# Connection.net
KiCad netlist of a schematic drawn in EAGLE
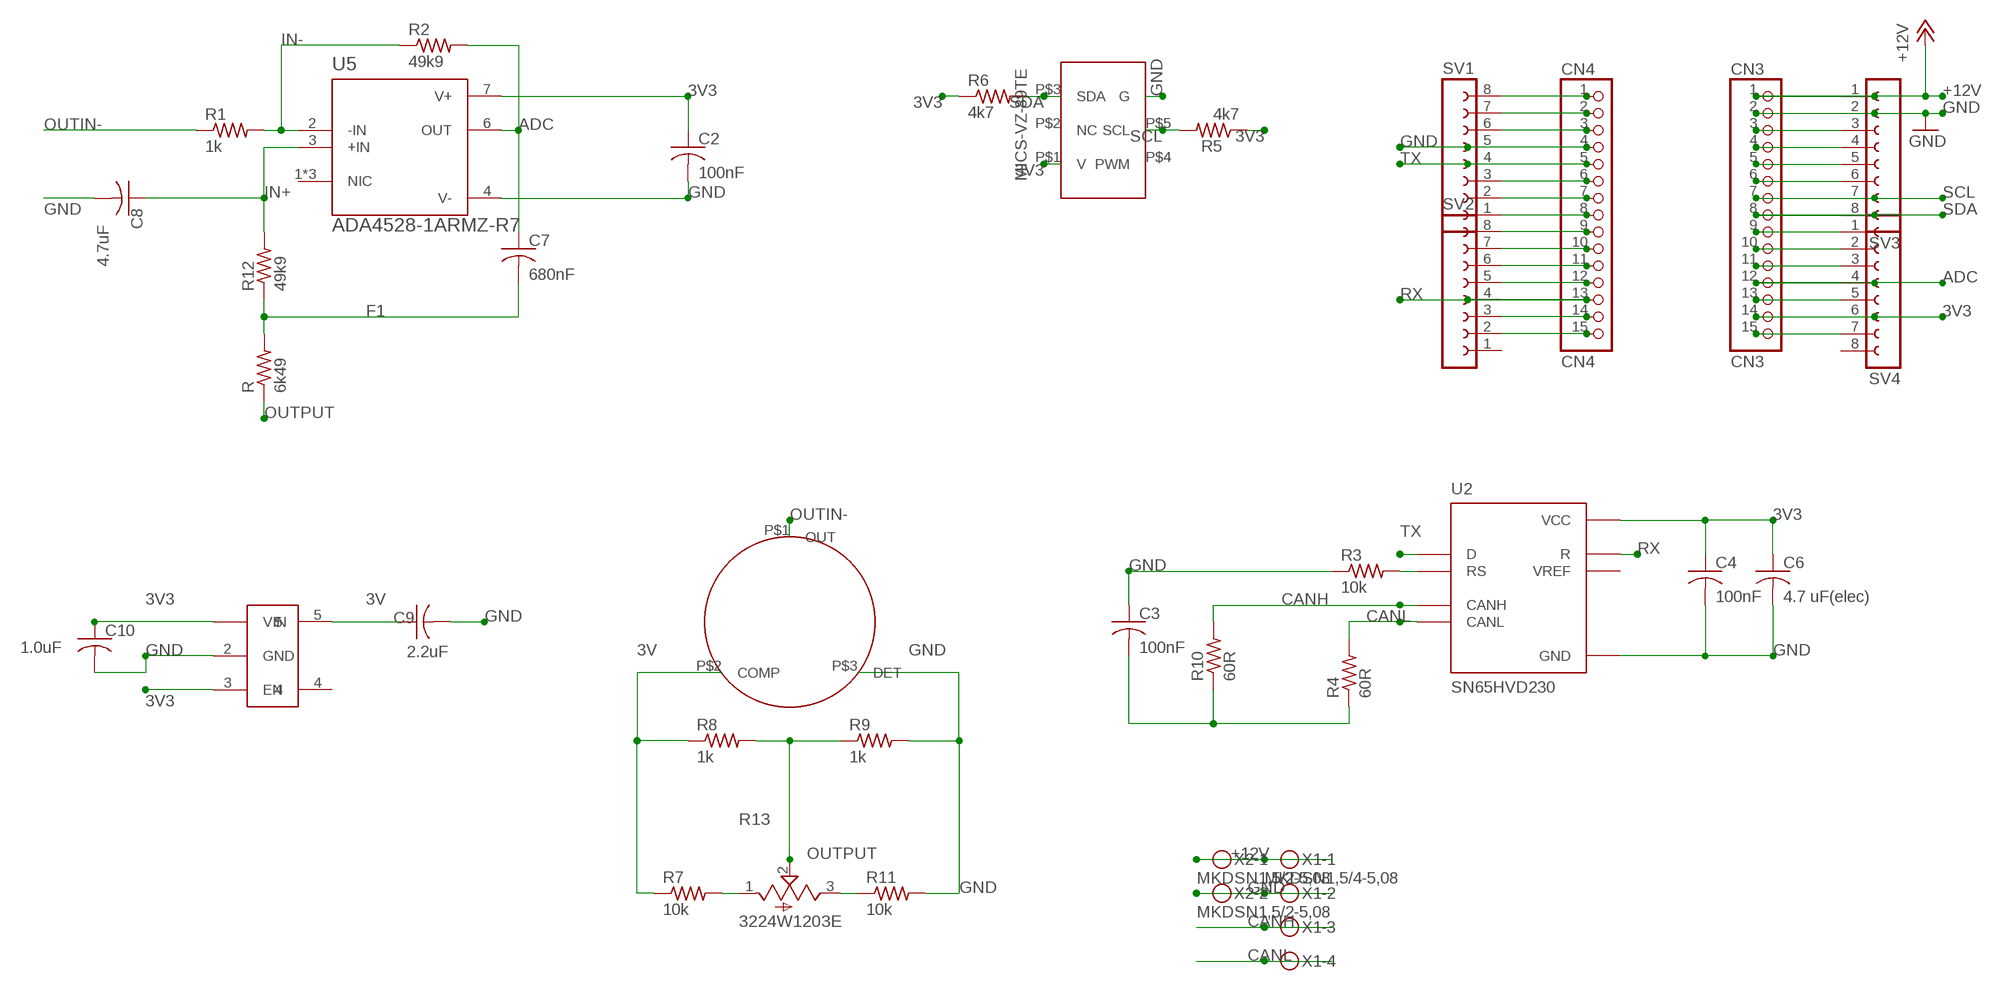
[diagram p0: schematic, sheet 1]

(export (version "E")
  (design (tool "Eeschema 10.0.6"))
  (components
    (comp (ref "C2")
      (value "100nF")
      (footprint "eagle-import:C0402")
      (libsource (lib "eagle-import") (part "C-USC0402"))
    )
    (comp (ref "C3")
      (value "100nF")
      (footprint "eagle-import:C0402")
      (libsource (lib "eagle-import") (part "C-USC0402"))
    )
    (comp (ref "C4")
      (value "100nF")
      (footprint "eagle-import:C0402")
      (libsource (lib "eagle-import") (part "C-USC0402"))
    )
    (comp (ref "C6")
      (value "4.7 uF(elec)")
      (footprint "eagle-import:C0603")
      (libsource (lib "eagle-import") (part "C-USC0603"))
    )
    (comp (ref "C7")
      (value "680nF")
      (footprint "eagle-import:C1206")
      (libsource (lib "eagle-import") (part "C-USC1206"))
    )
    (comp (ref "C8")
      (value "4.7uF")
      (footprint "eagle-import:C1206")
      (libsource (lib "eagle-import") (part "C-USC1206"))
    )
    (comp (ref "C9")
      (value "2.2uF")
      (footprint "eagle-import:C0603")
      (libsource (lib "eagle-import") (part "C-USC0603"))
    )
    (comp (ref "C10")
      (value "1.0uF")
      (footprint "eagle-import:C0805")
      (libsource (lib "eagle-import") (part "C-USC0805"))
    )
    (comp (ref "CN3")
      (value "CN3")
      (footprint "eagle-import:1X15")
      (libsource (lib "eagle-import") (part "PINHD-1X15"))
    )
    (comp (ref "CN4")
      (value "CN4")
      (footprint "eagle-import:1X15")
      (libsource (lib "eagle-import") (part "PINHD-1X15"))
    )
    (comp (ref "R")
      (value "6k49")
      (footprint "eagle-import:R0603")
      (libsource (lib "eagle-import") (part "R-US_R0603"))
    )
    (comp (ref "R1")
      (value "1k")
      (footprint "eagle-import:R0805")
      (libsource (lib "eagle-import") (part "R-US_R0805"))
    )
    (comp (ref "R2")
      (value "49k9")
      (footprint "eagle-import:R0603")
      (libsource (lib "eagle-import") (part "R-US_R0603"))
    )
    (comp (ref "R3")
      (value "10k")
      (footprint "eagle-import:M1206")
      (libsource (lib "eagle-import") (part "R-US_M1206"))
    )
    (comp (ref "R4")
      (value "60R")
      (footprint "eagle-import:R0603")
      (libsource (lib "eagle-import") (part "R-US_R0603"))
    )
    (comp (ref "R5")
      (value "4k7")
      (footprint "eagle-import:M1206")
      (libsource (lib "eagle-import") (part "R-US_M1206"))
    )
    (comp (ref "R6")
      (value "4k7")
      (footprint "eagle-import:M1206")
      (libsource (lib "eagle-import") (part "R-US_M1206"))
    )
    (comp (ref "R7")
      (value "10k")
      (footprint "eagle-import:M1206")
      (libsource (lib "eagle-import") (part "R-US_M1206"))
    )
    (comp (ref "R8")
      (value "1k")
      (footprint "eagle-import:R0805")
      (libsource (lib "eagle-import") (part "R-US_R0805"))
    )
    (comp (ref "R9")
      (value "1k")
      (footprint "eagle-import:R0805")
      (libsource (lib "eagle-import") (part "R-US_R0805"))
    )
    (comp (ref "R10")
      (value "60R")
      (footprint "eagle-import:R0603")
      (libsource (lib "eagle-import") (part "R-US_R0603"))
    )
    (comp (ref "R11")
      (value "10k")
      (footprint "eagle-import:M1206")
      (libsource (lib "eagle-import") (part "R-US_M1206"))
    )
    (comp (ref "R12")
      (value "49k9")
      (footprint "eagle-import:R0603")
      (libsource (lib "eagle-import") (part "R-US_R0603"))
    )
    (comp (ref "R13")
      (value "3224W1203E")
      (footprint "eagle-import:TRIM_3224W1203E")
      (fields (field (name "MF") "Bourns") (field (name "MP") "3224W-1-203E"))
      (libsource (lib "eagle-import") (part "3224W1203E"))
    )
    (comp (ref "SV1")
      (value "FE08-1")
      (footprint "eagle-import:FE08")
      (libsource (lib "eagle-import") (part "FE08-1"))
    )
    (comp (ref "SV2")
      (value "FE08-1")
      (footprint "eagle-import:FE08")
      (libsource (lib "eagle-import") (part "FE08-1"))
    )
    (comp (ref "SV3")
      (value "FE08-1")
      (footprint "eagle-import:FE08")
      (libsource (lib "eagle-import") (part "FE08-1"))
    )
    (comp (ref "SV4")
      (value "FE08-1")
      (footprint "eagle-import:FE08")
      (libsource (lib "eagle-import") (part "FE08-1"))
    )
    (comp (ref "U$1")
      (value "MP7227")
      (footprint "eagle-import:MP7227_FP")
      (libsource (lib "eagle-import") (part "MP7227"))
    )
    (comp (ref "U$3")
      (value "MIC5233")
      (footprint "eagle-import:MIC5233")
      (libsource (lib "eagle-import") (part "MIC5233"))
    )
    (comp (ref "U$4")
      (value "MICS-VZ-89TE")
      (footprint "eagle-import:MICS-VZ-89TE_FP")
      (libsource (lib "eagle-import") (part "MICS-VZ-89TE"))
    )
    (comp (ref "U2")
      (value "SN65HVD230")
      (footprint "eagle-import:SOIC127P599X175-8N")
      (fields (field (name "MF") "Texas Instruments"))
      (libsource (lib "eagle-import") (part "SN65HVD230"))
    )
    (comp (ref "U5")
      (value "ADA4528-1ARMZ-R7")
      (footprint "eagle-import:SOP65P490X110-8N")
      (fields (field (name "MF") "Analog Devices"))
      (libsource (lib "eagle-import") (part "ADA4528-1ARMZ-R7"))
    )
    (comp (ref "X1")
      (value "MKDSN1,5/4-5,08")
      (footprint "eagle-import:MKDSN1,5_4-5,08")
      (libsource (lib "eagle-import") (part "MKDSN1,5/4-5,08"))
    )
    (comp (ref "X2")
      (value "MKDSN1,5/2-5,08")
      (footprint "eagle-import:MKDSN1,5_2-5,08")
      (libsource (lib "eagle-import") (part "MKDSN1,5/2-5,08"))
    )
  )
  (nets
    (net (code "1") (name "+12V") (class "Default")
      (node (ref "CN3") (pin "1") (pinfunction "1_1") (pintype "passive"))
      (node (ref "SV3") (pin "1") (pinfunction "1_1") (pintype "passive"))
      (node (ref "X1") (pin "1") (pinfunction "KL_1") (pintype "passive"))
      (node (ref "X2") (pin "1") (pinfunction "KL_1") (pintype "passive"))
    )
    (net (code "2") (name "/3V") (class "Default")
      (node (ref "C9") (pin "1") (pinfunction "1_1") (pintype "passive"))
      (node (ref "R7") (pin "1") (pinfunction "1_1") (pintype "passive"))
      (node (ref "R8") (pin "1") (pinfunction "1_1") (pintype "passive"))
      (node (ref "U$1") (pin "P$2") (pinfunction "COMP_P$2") (pintype "bidirectional"))
      (node (ref "U$3") (pin "5") (pinfunction "5_5") (pintype "bidirectional"))
    )
    (net (code "3") (name "/3V3") (class "Default")
      (node (ref "C10") (pin "1") (pinfunction "1_1") (pintype "passive"))
      (node (ref "C2") (pin "1") (pinfunction "1_1") (pintype "passive"))
      (node (ref "C4") (pin "1") (pinfunction "1_1") (pintype "passive"))
      (node (ref "C6") (pin "1") (pinfunction "1_1") (pintype "passive"))
      (node (ref "CN3") (pin "14") (pinfunction "14_14") (pintype "passive"))
      (node (ref "R5") (pin "1") (pinfunction "1_1") (pintype "passive"))
      (node (ref "R6") (pin "1") (pinfunction "1_1") (pintype "passive"))
      (node (ref "SV4") (pin "6") (pinfunction "6_6") (pintype "passive"))
      (node (ref "U$3") (pin "1") (pinfunction "VIN_1") (pintype "bidirectional"))
      (node (ref "U$3") (pin "3") (pinfunction "EN_3") (pintype "bidirectional"))
      (node (ref "U$4") (pin "P$1") (pinfunction "V_P$1") (pintype "bidirectional"))
      (node (ref "U2") (pin "3") (pinfunction "VCC_3") (pintype "power_in"))
      (node (ref "U5") (pin "7") (pinfunction "V+_7") (pintype "power_in"))
    )
    (net (code "4") (name "/ADC") (class "Default")
      (node (ref "C7") (pin "1") (pinfunction "1_1") (pintype "passive"))
      (node (ref "CN3") (pin "12") (pinfunction "12_12") (pintype "passive"))
      (node (ref "R2") (pin "2") (pinfunction "2_2") (pintype "passive"))
      (node (ref "SV4") (pin "4") (pinfunction "4_4") (pintype "passive"))
      (node (ref "U5") (pin "6") (pinfunction "OUT_6") (pintype "output"))
    )
    (net (code "5") (name "/CANH") (class "Default")
      (node (ref "R10") (pin "2") (pinfunction "2_2") (pintype "passive"))
      (node (ref "U2") (pin "7") (pinfunction "CANH_7") (pintype "bidirectional"))
      (node (ref "X1") (pin "3") (pinfunction "KL_3") (pintype "passive"))
    )
    (net (code "6") (name "/CANL") (class "Default")
      (node (ref "R4") (pin "2") (pinfunction "2_2") (pintype "passive"))
      (node (ref "U2") (pin "6") (pinfunction "CANL_6") (pintype "bidirectional"))
      (node (ref "X1") (pin "4") (pinfunction "KL_4") (pintype "passive"))
    )
    (net (code "7") (name "/F1") (class "Default")
      (node (ref "C7") (pin "2") (pinfunction "2_2") (pintype "passive"))
      (node (ref "R") (pin "2") (pinfunction "2_2") (pintype "passive"))
      (node (ref "R12") (pin "1") (pinfunction "1_1") (pintype "passive"))
    )
    (net (code "8") (name "/IN+") (class "Default")
      (node (ref "C8") (pin "1") (pinfunction "1_1") (pintype "passive"))
      (node (ref "R12") (pin "2") (pinfunction "2_2") (pintype "passive"))
      (node (ref "U5") (pin "3") (pinfunction "+IN_3") (pintype "input"))
    )
    (net (code "9") (name "/IN-") (class "Default")
      (node (ref "R1") (pin "2") (pinfunction "2_2") (pintype "passive"))
      (node (ref "R2") (pin "1") (pinfunction "1_1") (pintype "passive"))
      (node (ref "U5") (pin "2") (pinfunction "-IN_2") (pintype "input"))
    )
    (net (code "10") (name "/OUTIN-") (class "Default")
      (node (ref "R1") (pin "1") (pinfunction "1_1") (pintype "passive"))
      (node (ref "U$1") (pin "P$1") (pinfunction "OUT_P$1") (pintype "bidirectional"))
    )
    (net (code "11") (name "/OUTPUT") (class "Default")
      (node (ref "R") (pin "1") (pinfunction "1_1") (pintype "passive"))
      (node (ref "R13") (pin "2") (pinfunction "2_2") (pintype "passive"))
      (node (ref "R8") (pin "2") (pinfunction "2_2") (pintype "passive"))
      (node (ref "R9") (pin "1") (pinfunction "1_1") (pintype "passive"))
    )
    (net (code "12") (name "/RX") (class "Default")
      (node (ref "CN4") (pin "13") (pinfunction "13_13") (pintype "passive"))
      (node (ref "SV2") (pin "4") (pinfunction "4_4") (pintype "passive"))
      (node (ref "U2") (pin "4") (pinfunction "R_4") (pintype "output"))
    )
    (net (code "13") (name "/SCL") (class "Default")
      (node (ref "CN3") (pin "7") (pinfunction "7_7") (pintype "passive"))
      (node (ref "R5") (pin "2") (pinfunction "2_2") (pintype "passive"))
      (node (ref "SV3") (pin "7") (pinfunction "7_7") (pintype "passive"))
      (node (ref "U$4") (pin "P$5") (pinfunction "SCL_P$5") (pintype "bidirectional"))
    )
    (net (code "14") (name "/SDA") (class "Default")
      (node (ref "CN3") (pin "8") (pinfunction "8_8") (pintype "passive"))
      (node (ref "R6") (pin "2") (pinfunction "2_2") (pintype "passive"))
      (node (ref "SV3") (pin "8") (pinfunction "8_8") (pintype "passive"))
      (node (ref "U$4") (pin "P$3") (pinfunction "SDA_P$3") (pintype "bidirectional"))
    )
    (net (code "15") (name "/TX") (class "Default")
      (node (ref "CN4") (pin "5") (pinfunction "5_5") (pintype "passive"))
      (node (ref "SV1") (pin "4") (pinfunction "4_4") (pintype "passive"))
      (node (ref "U2") (pin "1") (pinfunction "D_1") (pintype "input"))
    )
    (net (code "16") (name "GND") (class "Default")
      (node (ref "C10") (pin "2") (pinfunction "2_2") (pintype "passive"))
      (node (ref "C2") (pin "2") (pinfunction "2_2") (pintype "passive"))
      (node (ref "C3") (pin "1") (pinfunction "1_1") (pintype "passive"))
      (node (ref "C4") (pin "2") (pinfunction "2_2") (pintype "passive"))
      (node (ref "C6") (pin "2") (pinfunction "2_2") (pintype "passive"))
      (node (ref "C8") (pin "2") (pinfunction "2_2") (pintype "passive"))
      (node (ref "C9") (pin "2") (pinfunction "2_2") (pintype "passive"))
      (node (ref "CN3") (pin "2") (pinfunction "2_2") (pintype "passive"))
      (node (ref "CN4") (pin "4") (pinfunction "4_4") (pintype "passive"))
      (node (ref "R11") (pin "2") (pinfunction "2_2") (pintype "passive"))
      (node (ref "R3") (pin "1") (pinfunction "1_1") (pintype "passive"))
      (node (ref "R9") (pin "2") (pinfunction "2_2") (pintype "passive"))
      (node (ref "SV1") (pin "5") (pinfunction "5_5") (pintype "passive"))
      (node (ref "SV3") (pin "2") (pinfunction "2_2") (pintype "passive"))
      (node (ref "U$1") (pin "P$3") (pinfunction "DET_P$3") (pintype "bidirectional"))
      (node (ref "U$3") (pin "2") (pinfunction "GND_2") (pintype "bidirectional"))
      (node (ref "U$4") (pin "P$6") (pinfunction "G_P$6") (pintype "bidirectional"))
      (node (ref "U2") (pin "2") (pinfunction "GND_2") (pintype "power_in"))
      (node (ref "U5") (pin "4") (pinfunction "V-_4") (pintype "power_in"))
      (node (ref "X1") (pin "2") (pinfunction "KL_2") (pintype "passive"))
      (node (ref "X2") (pin "2") (pinfunction "KL_2") (pintype "passive"))
    )
    (net (code "17") (name "Net-(C3-Pad2)") (class "Default")
      (node (ref "C3") (pin "2") (pinfunction "2_2") (pintype "passive"))
      (node (ref "R10") (pin "1") (pinfunction "1_1") (pintype "passive"))
      (node (ref "R4") (pin "1") (pinfunction "1_1") (pintype "passive"))
    )
    (net (code "18") (name "Net-(CN3-Pad3)") (class "Default")
      (node (ref "CN3") (pin "3") (pinfunction "3_3") (pintype "passive"))
      (node (ref "SV3") (pin "3") (pinfunction "3_3") (pintype "passive"))
    )
    (net (code "19") (name "Net-(CN3-Pad4)") (class "Default")
      (node (ref "CN3") (pin "4") (pinfunction "4_4") (pintype "passive"))
      (node (ref "SV3") (pin "4") (pinfunction "4_4") (pintype "passive"))
    )
    (net (code "20") (name "Net-(CN3-Pad5)") (class "Default")
      (node (ref "CN3") (pin "5") (pinfunction "5_5") (pintype "passive"))
      (node (ref "SV3") (pin "5") (pinfunction "5_5") (pintype "passive"))
    )
    (net (code "21") (name "Net-(CN3-Pad6)") (class "Default")
      (node (ref "CN3") (pin "6") (pinfunction "6_6") (pintype "passive"))
      (node (ref "SV3") (pin "6") (pinfunction "6_6") (pintype "passive"))
    )
    (net (code "22") (name "Net-(CN3-Pad9)") (class "Default")
      (node (ref "CN3") (pin "9") (pinfunction "9_9") (pintype "passive"))
      (node (ref "SV4") (pin "1") (pinfunction "1_1") (pintype "passive"))
    )
    (net (code "23") (name "Net-(CN3-Pad10)") (class "Default")
      (node (ref "CN3") (pin "10") (pinfunction "10_10") (pintype "passive"))
      (node (ref "SV4") (pin "2") (pinfunction "2_2") (pintype "passive"))
    )
    (net (code "24") (name "Net-(CN3-Pad11)") (class "Default")
      (node (ref "CN3") (pin "11") (pinfunction "11_11") (pintype "passive"))
      (node (ref "SV4") (pin "3") (pinfunction "3_3") (pintype "passive"))
    )
    (net (code "25") (name "Net-(CN3-Pad13)") (class "Default")
      (node (ref "CN3") (pin "13") (pinfunction "13_13") (pintype "passive"))
      (node (ref "SV4") (pin "5") (pinfunction "5_5") (pintype "passive"))
    )
    (net (code "26") (name "Net-(CN3-Pad15)") (class "Default")
      (node (ref "CN3") (pin "15") (pinfunction "15_15") (pintype "passive"))
      (node (ref "SV4") (pin "7") (pinfunction "7_7") (pintype "passive"))
    )
    (net (code "27") (name "Net-(CN4-Pad1)") (class "Default")
      (node (ref "CN4") (pin "1") (pinfunction "1_1") (pintype "passive"))
      (node (ref "SV1") (pin "8") (pinfunction "8_8") (pintype "passive"))
    )
    (net (code "28") (name "Net-(CN4-Pad2)") (class "Default")
      (node (ref "CN4") (pin "2") (pinfunction "2_2") (pintype "passive"))
      (node (ref "SV1") (pin "7") (pinfunction "7_7") (pintype "passive"))
    )
    (net (code "29") (name "Net-(CN4-Pad3)") (class "Default")
      (node (ref "CN4") (pin "3") (pinfunction "3_3") (pintype "passive"))
      (node (ref "SV1") (pin "6") (pinfunction "6_6") (pintype "passive"))
    )
    (net (code "30") (name "Net-(CN4-Pad6)") (class "Default")
      (node (ref "CN4") (pin "6") (pinfunction "6_6") (pintype "passive"))
      (node (ref "SV1") (pin "3") (pinfunction "3_3") (pintype "passive"))
    )
    (net (code "31") (name "Net-(CN4-Pad7)") (class "Default")
      (node (ref "CN4") (pin "7") (pinfunction "7_7") (pintype "passive"))
      (node (ref "SV1") (pin "2") (pinfunction "2_2") (pintype "passive"))
    )
    (net (code "32") (name "Net-(CN4-Pad8)") (class "Default")
      (node (ref "CN4") (pin "8") (pinfunction "8_8") (pintype "passive"))
      (node (ref "SV1") (pin "1") (pinfunction "1_1") (pintype "passive"))
    )
    (net (code "33") (name "Net-(CN4-Pad9)") (class "Default")
      (node (ref "CN4") (pin "9") (pinfunction "9_9") (pintype "passive"))
      (node (ref "SV2") (pin "8") (pinfunction "8_8") (pintype "passive"))
    )
    (net (code "34") (name "Net-(CN4-Pad10)") (class "Default")
      (node (ref "CN4") (pin "10") (pinfunction "10_10") (pintype "passive"))
      (node (ref "SV2") (pin "7") (pinfunction "7_7") (pintype "passive"))
    )
    (net (code "35") (name "Net-(CN4-Pad11)") (class "Default")
      (node (ref "CN4") (pin "11") (pinfunction "11_11") (pintype "passive"))
      (node (ref "SV2") (pin "6") (pinfunction "6_6") (pintype "passive"))
    )
    (net (code "36") (name "Net-(CN4-Pad12)") (class "Default")
      (node (ref "CN4") (pin "12") (pinfunction "12_12") (pintype "passive"))
      (node (ref "SV2") (pin "5") (pinfunction "5_5") (pintype "passive"))
    )
    (net (code "37") (name "Net-(CN4-Pad14)") (class "Default")
      (node (ref "CN4") (pin "14") (pinfunction "14_14") (pintype "passive"))
      (node (ref "SV2") (pin "3") (pinfunction "3_3") (pintype "passive"))
    )
    (net (code "38") (name "Net-(CN4-Pad15)") (class "Default")
      (node (ref "CN4") (pin "15") (pinfunction "15_15") (pintype "passive"))
      (node (ref "SV2") (pin "2") (pinfunction "2_2") (pintype "passive"))
    )
    (net (code "39") (name "Net-(R11-Pad1)") (class "Default")
      (node (ref "R11") (pin "1") (pinfunction "1_1") (pintype "passive"))
      (node (ref "R13") (pin "3") (pinfunction "3_3") (pintype "passive"))
    )
    (net (code "40") (name "Net-(R13-Pad1)") (class "Default")
      (node (ref "R13") (pin "1") (pinfunction "1_1") (pintype "passive"))
      (node (ref "R7") (pin "2") (pinfunction "2_2") (pintype "passive"))
    )
    (net (code "41") (name "Net-(U2-RS)") (class "Default")
      (node (ref "R3") (pin "2") (pinfunction "2_2") (pintype "passive"))
      (node (ref "U2") (pin "8") (pinfunction "RS_8") (pintype "input"))
    )
    (net (code "42") (name "unconnected-(SV2-Pad1)") (class "Default")
      (node (ref "SV2") (pin "1") (pinfunction "1_1") (pintype "passive"))
    )
    (net (code "43") (name "unconnected-(SV4-Pad8)") (class "Default")
      (node (ref "SV4") (pin "8") (pinfunction "8_8") (pintype "passive"))
    )
    (net (code "44") (name "unconnected-(U$3-Pad4)") (class "Default")
      (node (ref "U$3") (pin "4") (pinfunction "4_4") (pintype "bidirectional"))
    )
    (net (code "45") (name "unconnected-(U$4-NC-PadP$2)") (class "Default")
      (node (ref "U$4") (pin "P$2") (pinfunction "NC_P$2") (pintype "bidirectional"))
    )
    (net (code "46") (name "unconnected-(U$4-PWM-PadP$4)") (class "Default")
      (node (ref "U$4") (pin "P$4") (pinfunction "PWM_P$4") (pintype "bidirectional"))
    )
    (net (code "47") (name "unconnected-(U2-VREF-Pad5)") (class "Default")
      (node (ref "U2") (pin "5") (pinfunction "VREF_5") (pintype "output"))
    )
    (net (code "48") (name "unconnected-(U5-NIC-Pad1)") (class "Default")
      (node (ref "U5") (pin "1") (pinfunction "NIC_1") (pintype "no_connect"))
    )
    (net (code "49") (name "unconnected-(U5-NIC-Pad5)") (class "Default")
      (node (ref "U5") (pin "5") (pinfunction "NIC_5") (pintype "no_connect"))
    )
    (net (code "50") (name "unconnected-(U5-NIC-Pad8)") (class "Default")
      (node (ref "U5") (pin "8") (pinfunction "NIC_8") (pintype "no_connect"))
    )
  )
)
